# MPQ3426_3V7to12V.net
KiCad netlist of a schematic drawn in EAGLE
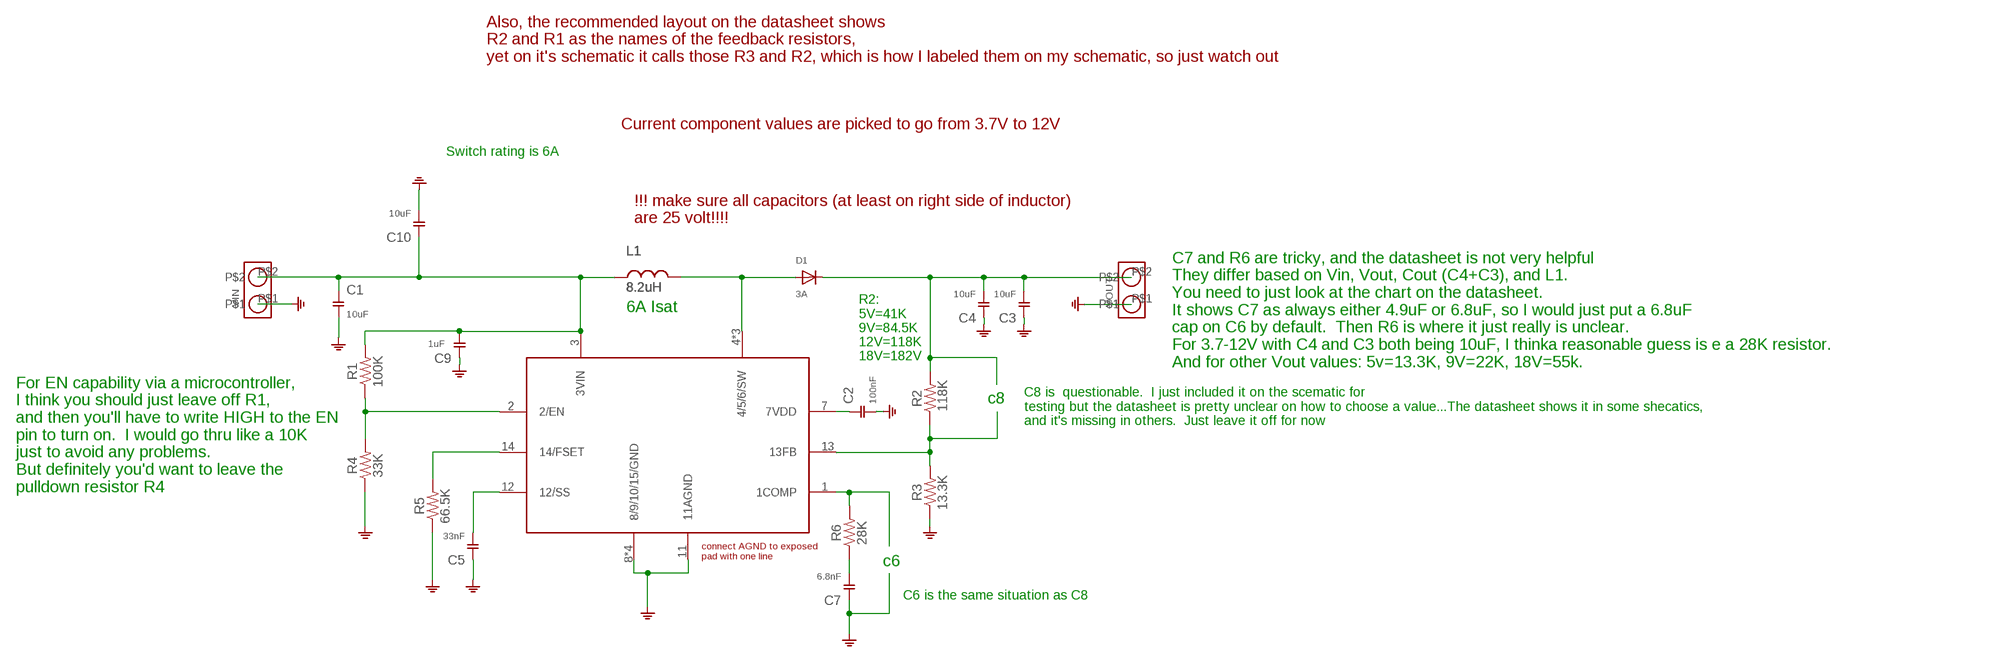
[diagram p0: schematic, sheet 1]

(export (version "E")
  (design (tool "Eeschema 10.0.6"))
  (components
    (comp (ref "C1")
      (value "10uF")
      (footprint "eagle-import:0805-NORMAL")
      (libsource (lib "eagle-import") (part "CAP_0805_NORMAL"))
    )
    (comp (ref "C2")
      (value "100nF")
      (footprint "eagle-import:0603_NORMAL")
      (libsource (lib "eagle-import") (part "CAP_0603"))
    )
    (comp (ref "C3")
      (value "10uF")
      (footprint "eagle-import:0805-NORMAL")
      (libsource (lib "eagle-import") (part "CAP_0805_NORMAL"))
    )
    (comp (ref "C4")
      (value "10uF")
      (footprint "eagle-import:0805-NORMAL")
      (libsource (lib "eagle-import") (part "CAP_0805_NORMAL"))
    )
    (comp (ref "C5")
      (value "33nF")
      (footprint "eagle-import:0603_NORMAL")
      (libsource (lib "eagle-import") (part "CAP_0603"))
    )
    (comp (ref "C7")
      (value "6.8nF")
      (footprint "eagle-import:0603_NORMAL")
      (libsource (lib "eagle-import") (part "CAP_0603"))
    )
    (comp (ref "C9")
      (value "1uF")
      (footprint "eagle-import:0603_NORMAL")
      (libsource (lib "eagle-import") (part "CAP_0603"))
    )
    (comp (ref "C10")
      (value "10uF")
      (footprint "eagle-import:0805-NORMAL")
      (libsource (lib "eagle-import") (part "CAP_0805_NORMAL"))
    )
    (comp (ref "D1")
      (value "3A")
      (footprint "eagle-import:SOD-123FL")
      (libsource (lib "eagle-import") (part "DIODE_SOD-123FL"))
    )
    (comp (ref "L1")
      (value "8.2uH")
      (footprint "eagle-import:INDUCTOR_UNIVERSAL_LARGE")
      (libsource (lib "eagle-import") (part "INDUCTOR_LARGE_UNIVERSAL"))
    )
    (comp (ref "R1")
      (value "100K")
      (footprint "eagle-import:0603_NORMAL")
      (libsource (lib "eagle-import") (part "RESISTOR_0603_TYPICAL"))
    )
    (comp (ref "R2")
      (value "118K")
      (footprint "eagle-import:0603_NORMAL")
      (libsource (lib "eagle-import") (part "RESISTOR_0603_TYPICAL"))
    )
    (comp (ref "R3")
      (value "13.3K")
      (footprint "eagle-import:0603_NORMAL")
      (libsource (lib "eagle-import") (part "RESISTOR_0603_TYPICAL"))
    )
    (comp (ref "R4")
      (value "33K")
      (footprint "eagle-import:0603_NORMAL")
      (libsource (lib "eagle-import") (part "RESISTOR_0603_TYPICAL"))
    )
    (comp (ref "R5")
      (value "66.5K")
      (footprint "eagle-import:0603_NORMAL")
      (libsource (lib "eagle-import") (part "RESISTOR_0603_TYPICAL"))
    )
    (comp (ref "R6")
      (value "28K")
      (footprint "eagle-import:0603_NORMAL")
      (libsource (lib "eagle-import") (part "RESISTOR_0603_TYPICAL"))
    )
    (comp (ref "U$1")
      (value "MPQ3426")
      (footprint "eagle-import:MPQ3426")
      (libsource (lib "eagle-import") (part "MPQ3426"))
    )
    (comp (ref "VIN")
      (value "HEADER_1X2_SQUARE_SMD")
      (footprint "eagle-import:1X2_.1__2.54_SMD")
      (libsource (lib "eagle-import") (part "HEADER_1X2_SQUARE_SMD"))
    )
    (comp (ref "VOUT")
      (value "HEADER_1X2_SQUARE_SMD")
      (footprint "eagle-import:1X2_.1__2.54_SMD")
      (libsource (lib "eagle-import") (part "HEADER_1X2_SQUARE_SMD"))
    )
  )
  (nets
    (net (code "1") (name "GND") (class "Default")
      (node (ref "C1") (pin "2") (pinfunction "2_2") (pintype "passive"))
      (node (ref "C10") (pin "2") (pinfunction "2_2") (pintype "passive"))
      (node (ref "C2") (pin "2") (pinfunction "2_2") (pintype "passive"))
      (node (ref "C3") (pin "1") (pinfunction "1_1") (pintype "passive"))
      (node (ref "C4") (pin "1") (pinfunction "1_1") (pintype "passive"))
      (node (ref "C5") (pin "1") (pinfunction "1_1") (pintype "passive"))
      (node (ref "C7") (pin "1") (pinfunction "1_1") (pintype "passive"))
      (node (ref "C9") (pin "1") (pinfunction "1_1") (pintype "passive"))
      (node (ref "R3") (pin "1") (pinfunction "1_1") (pintype "passive"))
      (node (ref "R4") (pin "1") (pinfunction "1_1") (pintype "passive"))
      (node (ref "R5") (pin "1") (pinfunction "1_1") (pintype "passive"))
      (node (ref "U$1") (pin "10") (pinfunction "8/9/10/15/GND_10") (pintype "bidirectional"))
      (node (ref "U$1") (pin "11") (pinfunction "11AGND_11") (pintype "bidirectional"))
      (node (ref "U$1") (pin "8") (pinfunction "8/9/10/15/GND_8") (pintype "bidirectional"))
      (node (ref "U$1") (pin "9") (pinfunction "8/9/10/15/GND_9") (pintype "bidirectional"))
      (node (ref "U$1") (pin "P$1") (pinfunction "8/9/10/15/GND_P$1") (pintype "bidirectional"))
      (node (ref "VIN") (pin "P$1") (pinfunction "P$1_P$1") (pintype "bidirectional"))
      (node (ref "VOUT") (pin "P$1") (pinfunction "P$1_P$1") (pintype "bidirectional"))
    )
    (net (code "2") (name "Net-(C3-Pad2)") (class "Default")
      (node (ref "C3") (pin "2") (pinfunction "2_2") (pintype "passive"))
      (node (ref "C4") (pin "2") (pinfunction "2_2") (pintype "passive"))
      (node (ref "D1") (pin "C") (pinfunction "C_C") (pintype "passive"))
      (node (ref "R2") (pin "2") (pinfunction "2_2") (pintype "passive"))
      (node (ref "VOUT") (pin "P$2") (pinfunction "P$2_P$2") (pintype "bidirectional"))
    )
    (net (code "3") (name "Net-(C7-Pad2)") (class "Default")
      (node (ref "C7") (pin "2") (pinfunction "2_2") (pintype "passive"))
      (node (ref "R6") (pin "1") (pinfunction "1_1") (pintype "passive"))
    )
    (net (code "4") (name "Net-(L1-1)") (class "Default")
      (node (ref "C1") (pin "1") (pinfunction "1_1") (pintype "passive"))
      (node (ref "C10") (pin "1") (pinfunction "1_1") (pintype "passive"))
      (node (ref "C9") (pin "2") (pinfunction "2_2") (pintype "passive"))
      (node (ref "L1") (pin "P$1") (pinfunction "1_P$1") (pintype "bidirectional"))
      (node (ref "R1") (pin "2") (pinfunction "2_2") (pintype "passive"))
      (node (ref "U$1") (pin "3") (pinfunction "3VIN_3") (pintype "bidirectional"))
      (node (ref "VIN") (pin "P$2") (pinfunction "P$2_P$2") (pintype "bidirectional"))
    )
    (net (code "5") (name "Net-(L1-2)") (class "Default")
      (node (ref "D1") (pin "A") (pinfunction "A_A") (pintype "passive"))
      (node (ref "L1") (pin "P$2") (pinfunction "2_P$2") (pintype "bidirectional"))
      (node (ref "U$1") (pin "4") (pinfunction "4/5/6/SW_4") (pintype "bidirectional"))
      (node (ref "U$1") (pin "5") (pinfunction "4/5/6/SW_5") (pintype "bidirectional"))
      (node (ref "U$1") (pin "6") (pinfunction "4/5/6/SW_6") (pintype "bidirectional"))
    )
    (net (code "6") (name "Net-(U$1-1COMP)") (class "Default")
      (node (ref "R6") (pin "2") (pinfunction "2_2") (pintype "passive"))
      (node (ref "U$1") (pin "1") (pinfunction "1COMP_1") (pintype "bidirectional"))
    )
    (net (code "7") (name "Net-(U$1-2{slash}EN)") (class "Default")
      (node (ref "R1") (pin "1") (pinfunction "1_1") (pintype "passive"))
      (node (ref "R4") (pin "2") (pinfunction "2_2") (pintype "passive"))
      (node (ref "U$1") (pin "2") (pinfunction "2/EN_2") (pintype "bidirectional"))
    )
    (net (code "8") (name "Net-(U$1-7VDD)") (class "Default")
      (node (ref "C2") (pin "1") (pinfunction "1_1") (pintype "passive"))
      (node (ref "U$1") (pin "7") (pinfunction "7VDD_7") (pintype "bidirectional"))
    )
    (net (code "9") (name "Net-(U$1-12{slash}SS)") (class "Default")
      (node (ref "C5") (pin "2") (pinfunction "2_2") (pintype "passive"))
      (node (ref "U$1") (pin "12") (pinfunction "12/SS_12") (pintype "bidirectional"))
    )
    (net (code "10") (name "Net-(U$1-13FB)") (class "Default")
      (node (ref "R2") (pin "1") (pinfunction "1_1") (pintype "passive"))
      (node (ref "R3") (pin "2") (pinfunction "2_2") (pintype "passive"))
      (node (ref "U$1") (pin "13") (pinfunction "13FB_13") (pintype "bidirectional"))
    )
    (net (code "11") (name "Net-(U$1-14{slash}FSET)") (class "Default")
      (node (ref "R5") (pin "2") (pinfunction "2_2") (pintype "passive"))
      (node (ref "U$1") (pin "14") (pinfunction "14/FSET_14") (pintype "bidirectional"))
    )
  )
)
